# MAX669_out.net
KiCad netlist of a schematic drawn in Altium Designer
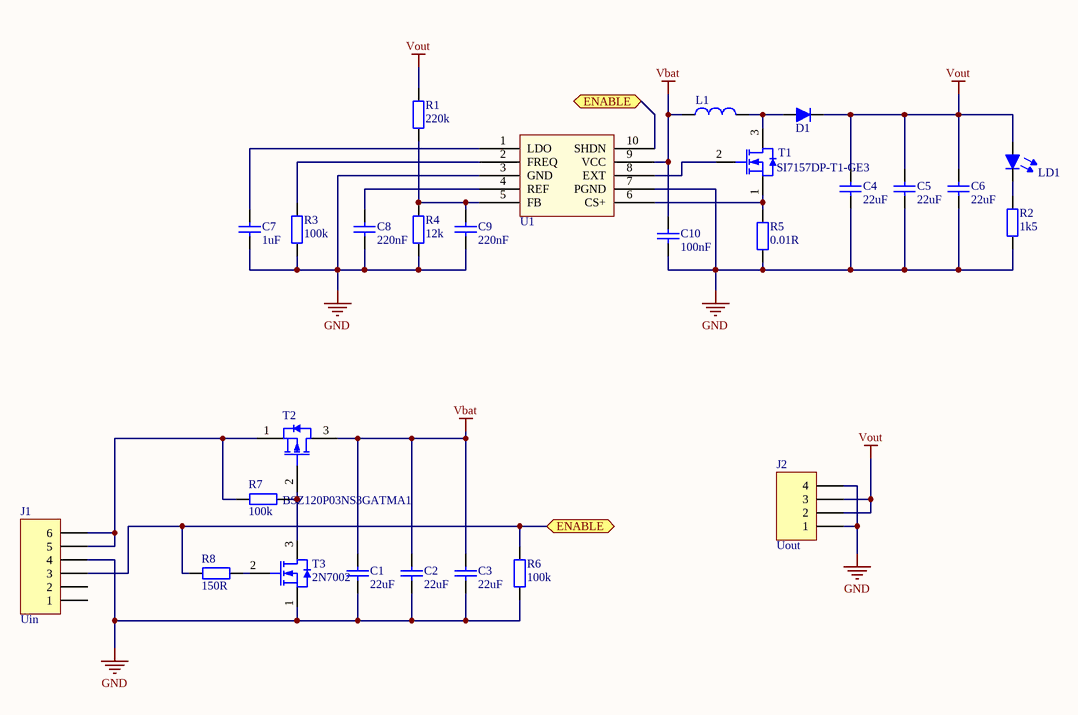
[diagram p0: MAX669 out.SchDoc]

(export (version "E")
  (design (tool "Eeschema 10.0.6"))
  (components
    (comp (ref "C1")
      (value "22uF")
      (footprint "1210 CAP")
      (description "Capacitor")
      (fields (field (name "VOLTAGE") "10V"))
      (libsource (lib "IKSOR_LIB_main") (part "Capacitor"))
    )
    (comp (ref "C2")
      (value "22uF")
      (footprint "1210 CAP")
      (description "Capacitor")
      (fields (field (name "VOLTAGE") "10V"))
      (libsource (lib "IKSOR_LIB_main") (part "Capacitor"))
    )
    (comp (ref "C3")
      (value "22uF")
      (footprint "1210 CAP")
      (description "Capacitor")
      (fields (field (name "VOLTAGE") "10V"))
      (libsource (lib "IKSOR_LIB_main") (part "Capacitor"))
    )
    (comp (ref "C4")
      (value "22uF")
      (footprint "1210 CAP")
      (description "Capacitor")
      (fields (field (name "VOLTAGE") "35V"))
      (libsource (lib "IKSOR_LIB_main") (part "Capacitor"))
    )
    (comp (ref "C5")
      (value "22uF")
      (footprint "1210 CAP")
      (description "Capacitor")
      (fields (field (name "VOLTAGE") "35V"))
      (libsource (lib "IKSOR_LIB_main") (part "Capacitor"))
    )
    (comp (ref "C6")
      (value "22uF")
      (footprint "1210 CAP")
      (description "Capacitor")
      (fields (field (name "VOLTAGE") "35V"))
      (libsource (lib "IKSOR_LIB_main") (part "Capacitor"))
    )
    (comp (ref "C7")
      (value "1uF")
      (footprint "0603 cap")
      (description "Capacitor")
      (fields (field (name "VOLTAGE") ">10V"))
      (libsource (lib "IKSOR_LIB_main") (part "Capacitor"))
    )
    (comp (ref "C8")
      (value "220nF")
      (footprint "0603 cap")
      (description "Capacitor")
      (fields (field (name "VOLTAGE") ">10V"))
      (libsource (lib "IKSOR_LIB_main") (part "Capacitor"))
    )
    (comp (ref "C9")
      (value "220nF")
      (footprint "0603 cap")
      (description "Capacitor")
      (fields (field (name "VOLTAGE") ">10V"))
      (libsource (lib "IKSOR_LIB_main") (part "Capacitor"))
    )
    (comp (ref "C10")
      (value "100nF")
      (footprint "0603 cap")
      (description "Capacitor")
      (fields (field (name "VOLTAGE") ">10V"))
      (libsource (lib "IKSOR_LIB_main") (part "Capacitor"))
    )
    (comp (ref "D1")
      (value "Diode")
      (footprint "TDSON Diode")
      (description "NRVTS1245EMFST1G")
      (libsource (lib "IKSOR_LIB_main") (part "Diode"))
    )
    (comp (ref "J1")
      (value "Uin")
      (footprint "HDR1X6")
      (description "Header, 6-Pin")
      (fields (field (name "PUBLISHER") "Altium Limited"))
      (libsource (lib "Miscellaneous Connectors") (part "Header 6"))
    )
    (comp (ref "J2")
      (value "Uout")
      (footprint "HDR1X4")
      (description "Header, 4-Pin")
      (fields (field (name "PUBLISHER") "Altium Limited"))
      (libsource (lib "Miscellaneous Connectors") (part "Header 4"))
    )
    (comp (ref "L1")
      (value "Inductor")
      (footprint "Inductor 7x7")
      (description "Single coil")
      (libsource (lib "IKSOR_LIB_main") (part "Inductor"))
    )
    (comp (ref "LD1")
      (value "LED diode")
      (footprint "LED_0603")
      (description "LED")
      (libsource (lib "IKSOR_LIB_main") (part "LED diode"))
    )
    (comp (ref "R1")
      (value "220k")
      (footprint "0603 RES")
      (description "Resistor SMD")
      (fields (field (name "Comment") "Resistor generic"))
      (libsource (lib "IKSOR_LIB_main") (part "Resistor"))
    )
    (comp (ref "R2")
      (value "1k5")
      (footprint "0603 RES")
      (description "Resistor SMD")
      (fields (field (name "Comment") "Resistor generic"))
      (libsource (lib "IKSOR_LIB_main") (part "Resistor"))
    )
    (comp (ref "R3")
      (value "100k")
      (footprint "0603 RES")
      (description "Resistor SMD")
      (fields (field (name "Comment") "Resistor generic"))
      (libsource (lib "IKSOR_LIB_main") (part "Resistor"))
    )
    (comp (ref "R4")
      (value "12k")
      (footprint "0603 RES")
      (description "Resistor SMD")
      (fields (field (name "Comment") "Resistor generic"))
      (libsource (lib "IKSOR_LIB_main") (part "Resistor"))
    )
    (comp (ref "R5")
      (value "0.01R")
      (footprint "2512 RES")
      (description "Resistor SMD")
      (fields (field (name "Comment") "Resistor generic"))
      (libsource (lib "IKSOR_LIB_main") (part "Resistor"))
    )
    (comp (ref "R6")
      (value "100k")
      (footprint "0603 RES")
      (description "Resistor SMD")
      (fields (field (name "Comment") "Resistor generic"))
      (libsource (lib "IKSOR_LIB_main") (part "Resistor"))
    )
    (comp (ref "R7")
      (value "100k")
      (footprint "0603 RES")
      (description "Resistor SMD")
      (fields (field (name "Comment") "Resistor generic"))
      (libsource (lib "IKSOR_LIB_main") (part "Resistor"))
    )
    (comp (ref "R8")
      (value "150R")
      (footprint "0603 RES")
      (description "Resistor SMD")
      (fields (field (name "Comment") "Resistor generic"))
      (libsource (lib "IKSOR_LIB_main") (part "Resistor"))
    )
    (comp (ref "T1")
      (value "SI7157DP-T1-GE3")
      (footprint "TDSON-8")
      (description "MOSFET N")
      (fields (field (name "Comment") "MOSFET-N"))
      (libsource (lib "IKSOR_LIB_main") (part "MOSFET-N"))
    )
    (comp (ref "T2")
      (value "BSZ120P03NS3GATMA1")
      (footprint "TDSON-8")
      (description "MOSFET P")
      (fields (field (name "VOLTAGE") "-30V") (field (name "Comment") "MOSFET-P"))
      (libsource (lib "IKSOR_LIB_main") (part "MOSFET-P"))
    )
    (comp (ref "T3")
      (value "2N7002")
      (footprint "SOT23")
      (description "MOSFET N")
      (fields (field (name "Comment") "MOSFET-N"))
      (libsource (lib "IKSOR_LIB_main") (part "MOSFET-N"))
    )
    (comp (ref "U1")
      (value "MAX669")
      (footprint "uMAX_10")
      (description "PWM Step-Up Controller")
      (libsource (lib "IKSOR_LIB_main") (part "MAX669"))
    )
  )
  (nets
    (net (code "1") (name "/ENABLE") (class "Default")
      (node (ref "J1") (pin "3") (pinfunction "3_3") (pintype "passive"))
      (node (ref "R6") (pin "2") (pinfunction "2_2") (pintype "passive"))
      (node (ref "R8") (pin "2") (pinfunction "2_2") (pintype "passive"))
      (node (ref "U1") (pin "10") (pinfunction "SHDN_10") (pintype "passive"))
    )
    (net (code "2") (name "GND") (class "Default")
      (node (ref "C1") (pin "1") (pinfunction "1_1") (pintype "passive"))
      (node (ref "C10") (pin "1") (pinfunction "1_1") (pintype "passive"))
      (node (ref "C2") (pin "1") (pinfunction "1_1") (pintype "passive"))
      (node (ref "C3") (pin "1") (pinfunction "1_1") (pintype "passive"))
      (node (ref "C4") (pin "1") (pinfunction "1_1") (pintype "passive"))
      (node (ref "C5") (pin "1") (pinfunction "1_1") (pintype "passive"))
      (node (ref "C6") (pin "1") (pinfunction "1_1") (pintype "passive"))
      (node (ref "C7") (pin "1") (pinfunction "1_1") (pintype "passive"))
      (node (ref "C8") (pin "1") (pinfunction "1_1") (pintype "passive"))
      (node (ref "C9") (pin "1") (pinfunction "1_1") (pintype "passive"))
      (node (ref "J1") (pin "4") (pinfunction "4_4") (pintype "passive"))
      (node (ref "J2") (pin "1") (pinfunction "1_1") (pintype "passive"))
      (node (ref "J2") (pin "4") (pinfunction "4_4") (pintype "passive"))
      (node (ref "R2") (pin "1") (pinfunction "1_1") (pintype "passive"))
      (node (ref "R3") (pin "1") (pinfunction "1_1") (pintype "passive"))
      (node (ref "R4") (pin "1") (pinfunction "1_1") (pintype "passive"))
      (node (ref "R5") (pin "1") (pinfunction "1_1") (pintype "passive"))
      (node (ref "R6") (pin "1") (pinfunction "1_1") (pintype "passive"))
      (node (ref "T3") (pin "1") (pinfunction "S_1") (pintype "passive"))
      (node (ref "U1") (pin "3") (pinfunction "GND_3") (pintype "passive"))
      (node (ref "U1") (pin "7") (pinfunction "PGND_7") (pintype "passive"))
    )
    (net (code "3") (name "Net-(D1-A)") (class "Default")
      (node (ref "D1") (pin "1") (pinfunction "A_1") (pintype "passive"))
      (node (ref "L1") (pin "2") (pinfunction "2_2") (pintype "passive"))
      (node (ref "T1") (pin "3") (pinfunction "D_3") (pintype "passive"))
    )
    (net (code "4") (name "Net-(LD1-K)") (class "Default")
      (node (ref "LD1") (pin "2") (pinfunction "K_2") (pintype "passive"))
      (node (ref "R2") (pin "2") (pinfunction "2_2") (pintype "passive"))
    )
    (net (code "5") (name "Net-(T1-G)") (class "Default")
      (node (ref "T1") (pin "2") (pinfunction "G_2") (pintype "passive"))
      (node (ref "U1") (pin "8") (pinfunction "EXT_8") (pintype "passive"))
    )
    (net (code "6") (name "Net-(T1-S)") (class "Default")
      (node (ref "R5") (pin "2") (pinfunction "2_2") (pintype "passive"))
      (node (ref "T1") (pin "1") (pinfunction "S_1") (pintype "passive"))
      (node (ref "U1") (pin "6") (pinfunction "CS+_6") (pintype "passive"))
    )
    (net (code "7") (name "Net-(T2-D)") (class "Default")
      (node (ref "J1") (pin "5") (pinfunction "5_5") (pintype "passive"))
      (node (ref "J1") (pin "6") (pinfunction "6_6") (pintype "passive"))
      (node (ref "R7") (pin "2") (pinfunction "2_2") (pintype "passive"))
      (node (ref "T2") (pin "1") (pinfunction "D_1") (pintype "passive"))
    )
    (net (code "8") (name "Net-(T2-G)") (class "Default")
      (node (ref "R7") (pin "1") (pinfunction "1_1") (pintype "passive"))
      (node (ref "T2") (pin "2") (pinfunction "G_2") (pintype "passive"))
      (node (ref "T3") (pin "3") (pinfunction "D_3") (pintype "passive"))
    )
    (net (code "9") (name "Net-(T3-G)") (class "Default")
      (node (ref "R8") (pin "1") (pinfunction "1_1") (pintype "passive"))
      (node (ref "T3") (pin "2") (pinfunction "G_2") (pintype "passive"))
    )
    (net (code "10") (name "Net-(U1-FB)") (class "Default")
      (node (ref "C9") (pin "2") (pinfunction "2_2") (pintype "passive"))
      (node (ref "R1") (pin "1") (pinfunction "1_1") (pintype "passive"))
      (node (ref "R4") (pin "2") (pinfunction "2_2") (pintype "passive"))
      (node (ref "U1") (pin "5") (pinfunction "FB_5") (pintype "passive"))
    )
    (net (code "11") (name "Net-(U1-FREQ)") (class "Default")
      (node (ref "R3") (pin "2") (pinfunction "2_2") (pintype "passive"))
      (node (ref "U1") (pin "2") (pinfunction "FREQ_2") (pintype "passive"))
    )
    (net (code "12") (name "Net-(U1-LDO)") (class "Default")
      (node (ref "C7") (pin "2") (pinfunction "2_2") (pintype "passive"))
      (node (ref "U1") (pin "1") (pinfunction "LDO_1") (pintype "passive"))
    )
    (net (code "13") (name "Net-(U1-REF)") (class "Default")
      (node (ref "C8") (pin "2") (pinfunction "2_2") (pintype "passive"))
      (node (ref "U1") (pin "4") (pinfunction "REF_4") (pintype "passive"))
    )
    (net (code "14") (name "Vbat") (class "Default")
      (node (ref "C1") (pin "2") (pinfunction "2_2") (pintype "passive"))
      (node (ref "C10") (pin "2") (pinfunction "2_2") (pintype "passive"))
      (node (ref "C2") (pin "2") (pinfunction "2_2") (pintype "passive"))
      (node (ref "C3") (pin "2") (pinfunction "2_2") (pintype "passive"))
      (node (ref "L1") (pin "1") (pinfunction "1_1") (pintype "passive"))
      (node (ref "T2") (pin "3") (pinfunction "S_3") (pintype "passive"))
      (node (ref "U1") (pin "9") (pinfunction "VCC_9") (pintype "passive"))
    )
    (net (code "15") (name "Vout") (class "Default")
      (node (ref "C4") (pin "2") (pinfunction "2_2") (pintype "passive"))
      (node (ref "C5") (pin "2") (pinfunction "2_2") (pintype "passive"))
      (node (ref "C6") (pin "2") (pinfunction "2_2") (pintype "passive"))
      (node (ref "D1") (pin "2") (pinfunction "K_2") (pintype "passive"))
      (node (ref "J2") (pin "2") (pinfunction "2_2") (pintype "passive"))
      (node (ref "J2") (pin "3") (pinfunction "3_3") (pintype "passive"))
      (node (ref "LD1") (pin "1") (pinfunction "A1_1") (pintype "passive"))
      (node (ref "R1") (pin "2") (pinfunction "2_2") (pintype "passive"))
    )
    (net (code "16") (name "unconnected-(J1-Pad1)") (class "Default")
      (node (ref "J1") (pin "1") (pinfunction "1_1") (pintype "passive"))
    )
    (net (code "17") (name "unconnected-(J1-Pad2)") (class "Default")
      (node (ref "J1") (pin "2") (pinfunction "2_2") (pintype "passive"))
    )
  )
)
